# DigiAnalog_Inputs.net
KiCad netlist of a schematic drawn in Altium Designer
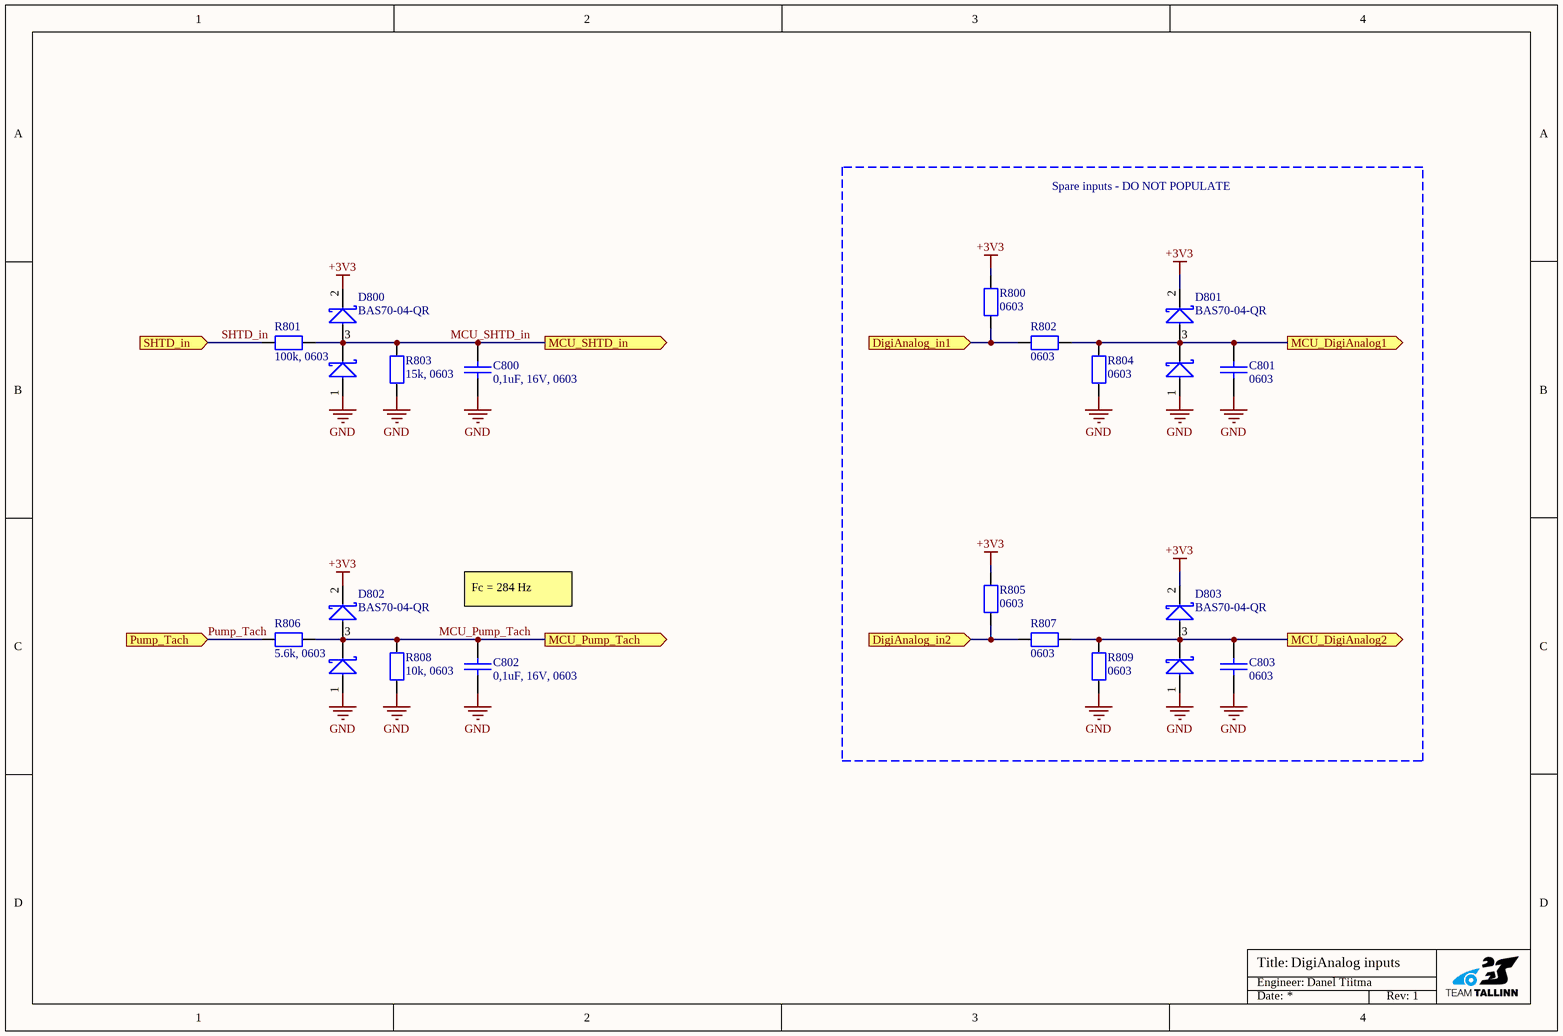
[diagram p0: DigiAnalog_Inputs.SchDoc]

(export (version "E")
  (design (tool "Eeschema 10.0.6"))
  (components
    (comp (ref "C800")
      (value "0,1uF, 16V, 0603")
      (footprint "CAP [0603] 1608")
      (description "Default capacitor part")
      (libsource (lib "Formula Student Team Tallinn (Estonia)") (part "Capacitor"))
    )
    (comp (ref "C801")
      (value "0603")
      (footprint "CAP [0603] 1608")
      (description "Default capacitor part")
      (libsource (lib "Formula Student Team Tallinn (Estonia)") (part "Capacitor"))
    )
    (comp (ref "C802")
      (value "0,1uF, 16V, 0603")
      (footprint "CAP [0603] 1608")
      (description "Default capacitor part")
      (libsource (lib "Formula Student Team Tallinn (Estonia)") (part "Capacitor"))
    )
    (comp (ref "C803")
      (value "0603")
      (footprint "CAP [0603] 1608")
      (description "Default capacitor part")
      (libsource (lib "Formula Student Team Tallinn (Estonia)") (part "Capacitor"))
    )
    (comp (ref "D800")
      (value "BAS70-04-QR")
      (footprint "SOT23-3")
      (description "Diode Small Signal Schottky 70V 70mA 3-Pin SOT-23 T/R")
      (fields (field (name "MANUFACTURER") "Nexperia"))
      (libsource (lib "Formula Student Team Tallinn (Estonia)") (part "Diode Rail-to-rail"))
    )
    (comp (ref "D801")
      (value "BAS70-04-QR")
      (footprint "SOT23-3")
      (description "Diode Small Signal Schottky 70V 70mA 3-Pin SOT-23 T/R")
      (fields (field (name "MANUFACTURER") "Nexperia"))
      (libsource (lib "Formula Student Team Tallinn (Estonia)") (part "Diode Rail-to-rail"))
    )
    (comp (ref "D802")
      (value "BAS70-04-QR")
      (footprint "SOT23-3")
      (description "Diode Small Signal Schottky 70V 70mA 3-Pin SOT-23 T/R")
      (fields (field (name "MANUFACTURER") "Nexperia"))
      (libsource (lib "Formula Student Team Tallinn (Estonia)") (part "Diode Rail-to-rail"))
    )
    (comp (ref "D803")
      (value "BAS70-04-QR")
      (footprint "SOT23-3")
      (description "Diode Small Signal Schottky 70V 70mA 3-Pin SOT-23 T/R")
      (fields (field (name "MANUFACTURER") "Nexperia"))
      (libsource (lib "Formula Student Team Tallinn (Estonia)") (part "Diode Rail-to-rail"))
    )
    (comp (ref "R800")
      (value "0603")
      (footprint "RES [0603] 1608")
      (description "Standard resistor part")
      (libsource (lib "Formula Student Team Tallinn (Estonia)") (part "Resistor"))
    )
    (comp (ref "R801")
      (value "100k, 0603")
      (footprint "RES [0603] 1608")
      (description "Standard resistor part")
      (libsource (lib "Formula Student Team Tallinn (Estonia)") (part "Resistor"))
    )
    (comp (ref "R802")
      (value "0603")
      (footprint "RES [0603] 1608")
      (description "Standard resistor part")
      (libsource (lib "Formula Student Team Tallinn (Estonia)") (part "Resistor"))
    )
    (comp (ref "R803")
      (value "15k, 0603")
      (footprint "RES [0603] 1608")
      (description "Standard resistor part")
      (libsource (lib "Formula Student Team Tallinn (Estonia)") (part "Resistor"))
    )
    (comp (ref "R804")
      (value "0603")
      (footprint "RES [0603] 1608")
      (description "Standard resistor part")
      (libsource (lib "Formula Student Team Tallinn (Estonia)") (part "Resistor"))
    )
    (comp (ref "R805")
      (value "0603")
      (footprint "RES [0603] 1608")
      (description "Standard resistor part")
      (libsource (lib "Formula Student Team Tallinn (Estonia)") (part "Resistor"))
    )
    (comp (ref "R806")
      (value "5.6k, 0603")
      (footprint "RES [0603] 1608")
      (description "Standard resistor part")
      (libsource (lib "Formula Student Team Tallinn (Estonia)") (part "Resistor"))
    )
    (comp (ref "R807")
      (value "0603")
      (footprint "RES [0603] 1608")
      (description "Standard resistor part")
      (libsource (lib "Formula Student Team Tallinn (Estonia)") (part "Resistor"))
    )
    (comp (ref "R808")
      (value "10k, 0603")
      (footprint "RES [0603] 1608")
      (description "Standard resistor part")
      (libsource (lib "Formula Student Team Tallinn (Estonia)") (part "Resistor"))
    )
    (comp (ref "R809")
      (value "0603")
      (footprint "RES [0603] 1608")
      (description "Standard resistor part")
      (libsource (lib "Formula Student Team Tallinn (Estonia)") (part "Resistor"))
    )
  )
  (nets
    (net (code "1") (name "+3V3") (class "Default")
      (node (ref "D800") (pin "2") (pinfunction "2_2") (pintype "passive"))
      (node (ref "D801") (pin "2") (pinfunction "2_2") (pintype "passive"))
      (node (ref "D802") (pin "2") (pinfunction "2_2") (pintype "passive"))
      (node (ref "D803") (pin "2") (pinfunction "2_2") (pintype "passive"))
      (node (ref "R800") (pin "2") (pinfunction "2_2") (pintype "passive"))
      (node (ref "R805") (pin "2") (pinfunction "2_2") (pintype "passive"))
    )
    (net (code "2") (name "/DigiAnalog_in1") (class "Default")
      (node (ref "R800") (pin "1") (pinfunction "1_1") (pintype "passive"))
      (node (ref "R802") (pin "2") (pinfunction "2_2") (pintype "passive"))
    )
    (net (code "3") (name "/DigiAnalog_in2") (class "Default")
      (node (ref "R805") (pin "1") (pinfunction "1_1") (pintype "passive"))
      (node (ref "R807") (pin "2") (pinfunction "2_2") (pintype "passive"))
    )
    (net (code "4") (name "/MCU_DigiAnalog1") (class "Default")
      (node (ref "C801") (pin "1") (pinfunction "1_1") (pintype "passive"))
      (node (ref "D801") (pin "3") (pinfunction "3_3") (pintype "passive"))
      (node (ref "R802") (pin "1") (pinfunction "1_1") (pintype "passive"))
      (node (ref "R804") (pin "2") (pinfunction "2_2") (pintype "passive"))
    )
    (net (code "5") (name "/MCU_DigiAnalog2") (class "Default")
      (node (ref "C803") (pin "1") (pinfunction "1_1") (pintype "passive"))
      (node (ref "D803") (pin "3") (pinfunction "3_3") (pintype "passive"))
      (node (ref "R807") (pin "1") (pinfunction "1_1") (pintype "passive"))
      (node (ref "R809") (pin "2") (pinfunction "2_2") (pintype "passive"))
    )
    (net (code "6") (name "/MCU_Pump_Tach") (class "Default")
      (node (ref "C802") (pin "1") (pinfunction "1_1") (pintype "passive"))
      (node (ref "D802") (pin "3") (pinfunction "3_3") (pintype "passive"))
      (node (ref "R806") (pin "2") (pinfunction "2_2") (pintype "passive"))
      (node (ref "R808") (pin "2") (pinfunction "2_2") (pintype "passive"))
    )
    (net (code "7") (name "/MCU_SHTD_in") (class "Default")
      (node (ref "C800") (pin "1") (pinfunction "1_1") (pintype "passive"))
      (node (ref "D800") (pin "3") (pinfunction "3_3") (pintype "passive"))
      (node (ref "R801") (pin "2") (pinfunction "2_2") (pintype "passive"))
      (node (ref "R803") (pin "2") (pinfunction "2_2") (pintype "passive"))
    )
    (net (code "8") (name "/Pump_Tach") (class "Default")
      (node (ref "R806") (pin "1") (pinfunction "1_1") (pintype "passive"))
    )
    (net (code "9") (name "/SHTD_in") (class "Default")
      (node (ref "R801") (pin "1") (pinfunction "1_1") (pintype "passive"))
    )
    (net (code "10") (name "GND") (class "Default")
      (node (ref "C800") (pin "2") (pinfunction "2_2") (pintype "passive"))
      (node (ref "C801") (pin "2") (pinfunction "2_2") (pintype "passive"))
      (node (ref "C802") (pin "2") (pinfunction "2_2") (pintype "passive"))
      (node (ref "C803") (pin "2") (pinfunction "2_2") (pintype "passive"))
      (node (ref "D800") (pin "1") (pinfunction "1_1") (pintype "passive"))
      (node (ref "D801") (pin "1") (pinfunction "1_1") (pintype "passive"))
      (node (ref "D802") (pin "1") (pinfunction "1_1") (pintype "passive"))
      (node (ref "D803") (pin "1") (pinfunction "1_1") (pintype "passive"))
      (node (ref "R803") (pin "1") (pinfunction "1_1") (pintype "passive"))
      (node (ref "R804") (pin "1") (pinfunction "1_1") (pintype "passive"))
      (node (ref "R808") (pin "1") (pinfunction "1_1") (pintype "passive"))
      (node (ref "R809") (pin "1") (pinfunction "1_1") (pintype "passive"))
    )
  )
)
